# open-source-event-marker-photodiode-sche.net
KiCad netlist of a schematic drawn in EAGLE
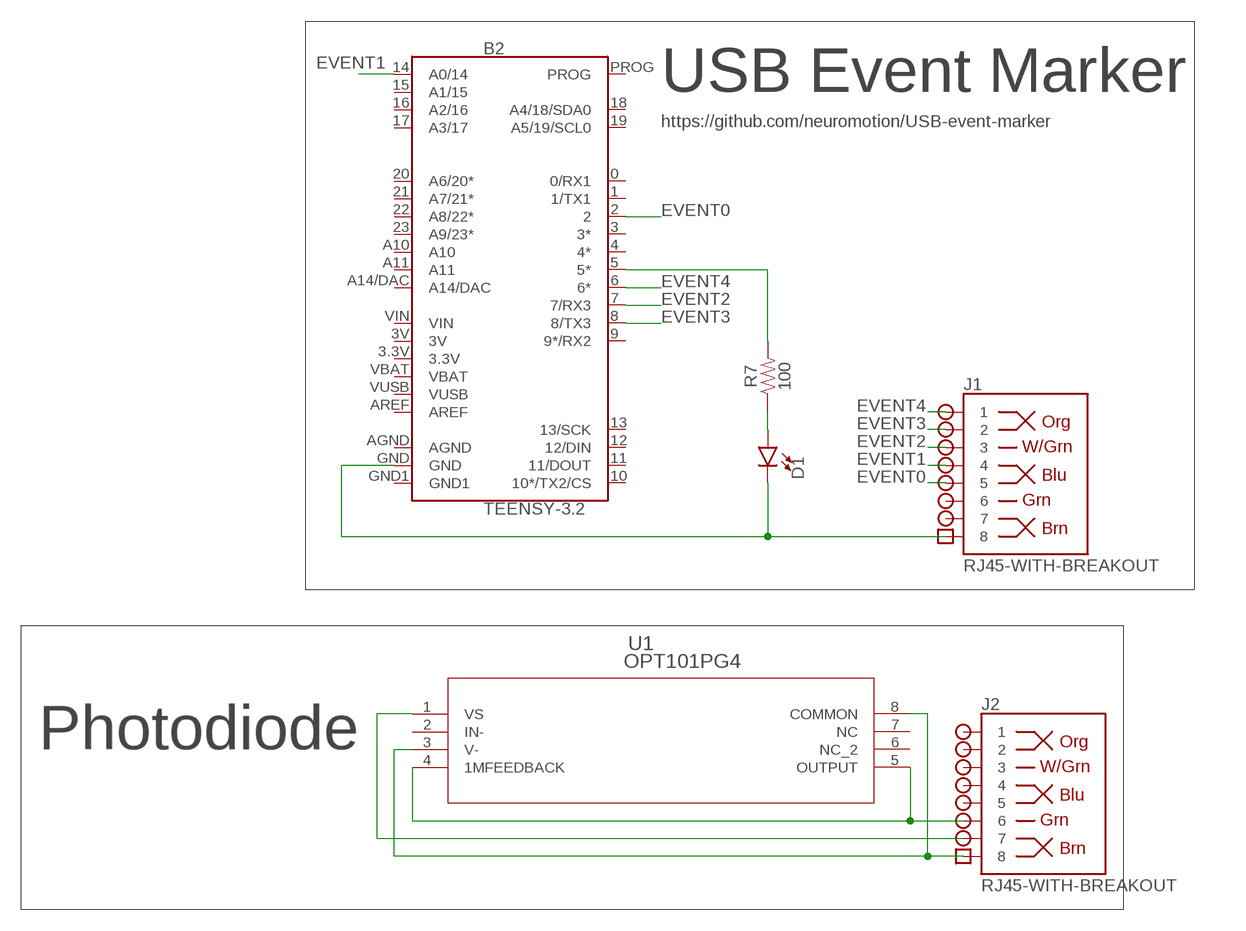
[diagram p0: schematic, sheet 1]

(export (version "E")
  (design (tool "Eeschema 10.0.6"))
  (components
    (comp (ref "B2")
      (value "TEENSY-3.2")
      (footprint "eagle-import:TEENSY-3.1")
      (libsource (lib "eagle-import") (part "TEENSY-3.1SILK"))
    )
    (comp (ref "D1")
      (value "LED-3MM-NO_SILK")
      (footprint "eagle-import:LED_3MM-NS")
      (libsource (lib "eagle-import") (part "LED-3MM-NO_SILK"))
    )
    (comp (ref "J1")
      (value "RJ45-WITH-BREAKOUT")
      (footprint "eagle-import:RJ45-WITH-BREAKOUT-PACKAGE")
      (libsource (lib "eagle-import") (part "RJ45-WITH-BREAKOUT"))
    )
    (comp (ref "J2")
      (value "RJ45-WITH-BREAKOUT")
      (footprint "eagle-import:RJ45-WITH-BREAKOUT-PACKAGE")
      (libsource (lib "eagle-import") (part "RJ45-WITH-BREAKOUT"))
    )
    (comp (ref "R7")
      (value "100")
      (footprint "eagle-import:AXIAL-0.3")
      (libsource (lib "eagle-import") (part "100OHM-HORIZ-1/4W-1%"))
    )
    (comp (ref "U1")
      (value "OPT101PG4")
      (footprint "eagle-import:NTC8")
      (libsource (lib "eagle-import") (part "OPT101PG4"))
    )
  )
  (nets
    (net (code "1") (name "/3.3V") (class "Default")
      (node (ref "B2") (pin "3.3V") (pinfunction "3.3V_3.3V") (pintype "power_in"))
    )
    (net (code "2") (name "/3V") (class "Default")
      (node (ref "B2") (pin "3V") (pinfunction "3V_3V") (pintype "power_in"))
    )
    (net (code "3") (name "/AGND") (class "Default")
      (node (ref "B2") (pin "AGND") (pinfunction "AGND_AGND") (pintype "power_in"))
    )
    (net (code "4") (name "/EVENT0") (class "Default")
      (node (ref "B2") (pin "2") (pinfunction "2_2") (pintype "bidirectional"))
      (node (ref "J1") (pin "5") (pinfunction "5_5") (pintype "bidirectional"))
    )
    (net (code "5") (name "/EVENT1") (class "Default")
      (node (ref "B2") (pin "14") (pinfunction "A0/14_14") (pintype "bidirectional"))
      (node (ref "J1") (pin "4") (pinfunction "4_4") (pintype "bidirectional"))
    )
    (net (code "6") (name "/EVENT2") (class "Default")
      (node (ref "B2") (pin "7") (pinfunction "7/RX3_7") (pintype "bidirectional"))
      (node (ref "J1") (pin "3") (pinfunction "3_3") (pintype "bidirectional"))
    )
    (net (code "7") (name "/EVENT3") (class "Default")
      (node (ref "B2") (pin "8") (pinfunction "8/TX3_8") (pintype "bidirectional"))
      (node (ref "J1") (pin "2") (pinfunction "2_2") (pintype "bidirectional"))
    )
    (net (code "8") (name "/EVENT4") (class "Default")
      (node (ref "B2") (pin "6") (pinfunction "6*_6") (pintype "bidirectional"))
      (node (ref "J1") (pin "1") (pinfunction "1_1") (pintype "bidirectional"))
    )
    (net (code "9") (name "/GND1") (class "Default")
      (node (ref "B2") (pin "GND1") (pinfunction "GND1_GND1") (pintype "power_in"))
    )
    (net (code "10") (name "/VBAT") (class "Default")
      (node (ref "B2") (pin "VBAT") (pinfunction "VBAT_VBAT") (pintype "power_in"))
    )
    (net (code "11") (name "/VIN") (class "Default")
      (node (ref "B2") (pin "VIN") (pinfunction "VIN_VIN") (pintype "power_in"))
    )
    (net (code "12") (name "/VUSB") (class "Default")
      (node (ref "B2") (pin "VUSB") (pinfunction "VUSB_VUSB") (pintype "power_in"))
    )
    (net (code "13") (name "Net-(B2-5*)") (class "Default")
      (node (ref "B2") (pin "5") (pinfunction "5*_5") (pintype "bidirectional"))
      (node (ref "R7") (pin "P$2") (pinfunction "2_P$2") (pintype "passive"))
    )
    (net (code "14") (name "Net-(D1-C)") (class "Default")
      (node (ref "B2") (pin "GND") (pinfunction "GND_GND") (pintype "power_in"))
      (node (ref "D1") (pin "K") (pinfunction "C_K") (pintype "passive"))
      (node (ref "J1") (pin "8") (pinfunction "8_8") (pintype "bidirectional"))
    )
    (net (code "15") (name "Net-(R7-1)") (class "Default")
      (node (ref "D1") (pin "A") (pinfunction "A_A") (pintype "passive"))
      (node (ref "R7") (pin "P$1") (pinfunction "1_P$1") (pintype "passive"))
    )
    (net (code "16") (name "Net-(U1-1MFEEDBACK)") (class "Default")
      (node (ref "J2") (pin "6") (pinfunction "6_6") (pintype "bidirectional"))
      (node (ref "U1") (pin "4") (pinfunction "1MFEEDBACK_4") (pintype "passive"))
      (node (ref "U1") (pin "5") (pinfunction "OUTPUT_5") (pintype "output"))
    )
    (net (code "17") (name "Net-(U1-COMMON)") (class "Default")
      (node (ref "J2") (pin "8") (pinfunction "8_8") (pintype "bidirectional"))
      (node (ref "U1") (pin "3") (pinfunction "V-_3") (pintype "power_in"))
      (node (ref "U1") (pin "8") (pinfunction "COMMON_8") (pintype "passive"))
    )
    (net (code "18") (name "Net-(U1-VS)") (class "Default")
      (node (ref "J2") (pin "7") (pinfunction "7_7") (pintype "bidirectional"))
      (node (ref "U1") (pin "1") (pinfunction "VS_1") (pintype "power_in"))
    )
    (net (code "19") (name "unconnected-(B2-0{slash}RX1-Pad0)") (class "Default")
      (node (ref "B2") (pin "0") (pinfunction "0/RX1_0") (pintype "bidirectional"))
    )
    (net (code "20") (name "unconnected-(B2-1{slash}TX1-Pad1)") (class "Default")
      (node (ref "B2") (pin "1") (pinfunction "1/TX1_1") (pintype "bidirectional"))
    )
    (net (code "21") (name "unconnected-(B2-3*-Pad3)") (class "Default")
      (node (ref "B2") (pin "3") (pinfunction "3*_3") (pintype "bidirectional"))
    )
    (net (code "22") (name "unconnected-(B2-4*-Pad4)") (class "Default")
      (node (ref "B2") (pin "4") (pinfunction "4*_4") (pintype "bidirectional"))
    )
    (net (code "23") (name "unconnected-(B2-9*{slash}RX2-Pad9)") (class "Default")
      (node (ref "B2") (pin "9") (pinfunction "9*/RX2_9") (pintype "bidirectional"))
    )
    (net (code "24") (name "unconnected-(B2-10*{slash}TX2{slash}CS-Pad10)") (class "Default")
      (node (ref "B2") (pin "10") (pinfunction "10*/TX2/CS_10") (pintype "bidirectional"))
    )
    (net (code "25") (name "unconnected-(B2-11{slash}DOUT-Pad11)") (class "Default")
      (node (ref "B2") (pin "11") (pinfunction "11/DOUT_11") (pintype "bidirectional"))
    )
    (net (code "26") (name "unconnected-(B2-12{slash}DIN-Pad12)") (class "Default")
      (node (ref "B2") (pin "12") (pinfunction "12/DIN_12") (pintype "bidirectional"))
    )
    (net (code "27") (name "unconnected-(B2-13{slash}SCK-Pad13)") (class "Default")
      (node (ref "B2") (pin "13") (pinfunction "13/SCK_13") (pintype "bidirectional"))
    )
    (net (code "28") (name "unconnected-(B2-A1{slash}15-Pad15)") (class "Default")
      (node (ref "B2") (pin "15") (pinfunction "A1/15_15") (pintype "bidirectional"))
    )
    (net (code "29") (name "unconnected-(B2-A2{slash}16-Pad16)") (class "Default")
      (node (ref "B2") (pin "16") (pinfunction "A2/16_16") (pintype "bidirectional"))
    )
    (net (code "30") (name "unconnected-(B2-A3{slash}17-Pad17)") (class "Default")
      (node (ref "B2") (pin "17") (pinfunction "A3/17_17") (pintype "bidirectional"))
    )
    (net (code "31") (name "unconnected-(B2-A4{slash}18{slash}SDA0-Pad18)") (class "Default")
      (node (ref "B2") (pin "18") (pinfunction "A4/18/SDA0_18") (pintype "bidirectional"))
    )
    (net (code "32") (name "unconnected-(B2-A5{slash}19{slash}SCL0-Pad19)") (class "Default")
      (node (ref "B2") (pin "19") (pinfunction "A5/19/SCL0_19") (pintype "bidirectional"))
    )
    (net (code "33") (name "unconnected-(B2-A6{slash}20*-Pad20)") (class "Default")
      (node (ref "B2") (pin "20") (pinfunction "A6/20*_20") (pintype "bidirectional"))
    )
    (net (code "34") (name "unconnected-(B2-A7{slash}21*-Pad21)") (class "Default")
      (node (ref "B2") (pin "21") (pinfunction "A7/21*_21") (pintype "bidirectional"))
    )
    (net (code "35") (name "unconnected-(B2-A8{slash}22*-Pad22)") (class "Default")
      (node (ref "B2") (pin "22") (pinfunction "A8/22*_22") (pintype "bidirectional"))
    )
    (net (code "36") (name "unconnected-(B2-A9{slash}23*-Pad23)") (class "Default")
      (node (ref "B2") (pin "23") (pinfunction "A9/23*_23") (pintype "bidirectional"))
    )
    (net (code "37") (name "unconnected-(B2-PadA10)") (class "Default")
      (node (ref "B2") (pin "A10") (pinfunction "A10_A10") (pintype "bidirectional"))
    )
    (net (code "38") (name "unconnected-(B2-PadA11)") (class "Default")
      (node (ref "B2") (pin "A11") (pinfunction "A11_A11") (pintype "bidirectional"))
    )
    (net (code "39") (name "unconnected-(B2-PadA14{slash}DAC)") (class "Default")
      (node (ref "B2") (pin "A14/DAC") (pinfunction "A14/DAC_A14/DAC") (pintype "bidirectional"))
    )
    (net (code "40") (name "unconnected-(B2-PadAREF)") (class "Default")
      (node (ref "B2") (pin "AREF") (pinfunction "AREF_AREF") (pintype "bidirectional"))
    )
    (net (code "41") (name "unconnected-(B2-PadPROG)") (class "Default")
      (node (ref "B2") (pin "PROG") (pinfunction "PROG_PROG") (pintype "bidirectional"))
    )
    (net (code "42") (name "unconnected-(J1-Pad6)") (class "Default")
      (node (ref "J1") (pin "6") (pinfunction "6_6") (pintype "bidirectional"))
    )
    (net (code "43") (name "unconnected-(J1-Pad7)") (class "Default")
      (node (ref "J1") (pin "7") (pinfunction "7_7") (pintype "bidirectional"))
    )
    (net (code "44") (name "unconnected-(J2-Pad1)") (class "Default")
      (node (ref "J2") (pin "1") (pinfunction "1_1") (pintype "bidirectional"))
    )
    (net (code "45") (name "unconnected-(J2-Pad2)") (class "Default")
      (node (ref "J2") (pin "2") (pinfunction "2_2") (pintype "bidirectional"))
    )
    (net (code "46") (name "unconnected-(J2-Pad3)") (class "Default")
      (node (ref "J2") (pin "3") (pinfunction "3_3") (pintype "bidirectional"))
    )
    (net (code "47") (name "unconnected-(J2-Pad4)") (class "Default")
      (node (ref "J2") (pin "4") (pinfunction "4_4") (pintype "bidirectional"))
    )
    (net (code "48") (name "unconnected-(J2-Pad5)") (class "Default")
      (node (ref "J2") (pin "5") (pinfunction "5_5") (pintype "bidirectional"))
    )
    (net (code "49") (name "unconnected-(U1-IN--Pad2)") (class "Default")
      (node (ref "U1") (pin "2") (pinfunction "IN-_2") (pintype "input"))
    )
    (net (code "50") (name "unconnected-(U1-NC-Pad7)") (class "Default")
      (node (ref "U1") (pin "7") (pinfunction "NC_7") (pintype "no_connect"))
    )
    (net (code "51") (name "unconnected-(U1-NC_2-Pad6)") (class "Default")
      (node (ref "U1") (pin "6") (pinfunction "NC_2_6") (pintype "no_connect"))
    )
  )
)
